# arm_new.net
KiCad netlist of a schematic drawn in EAGLE
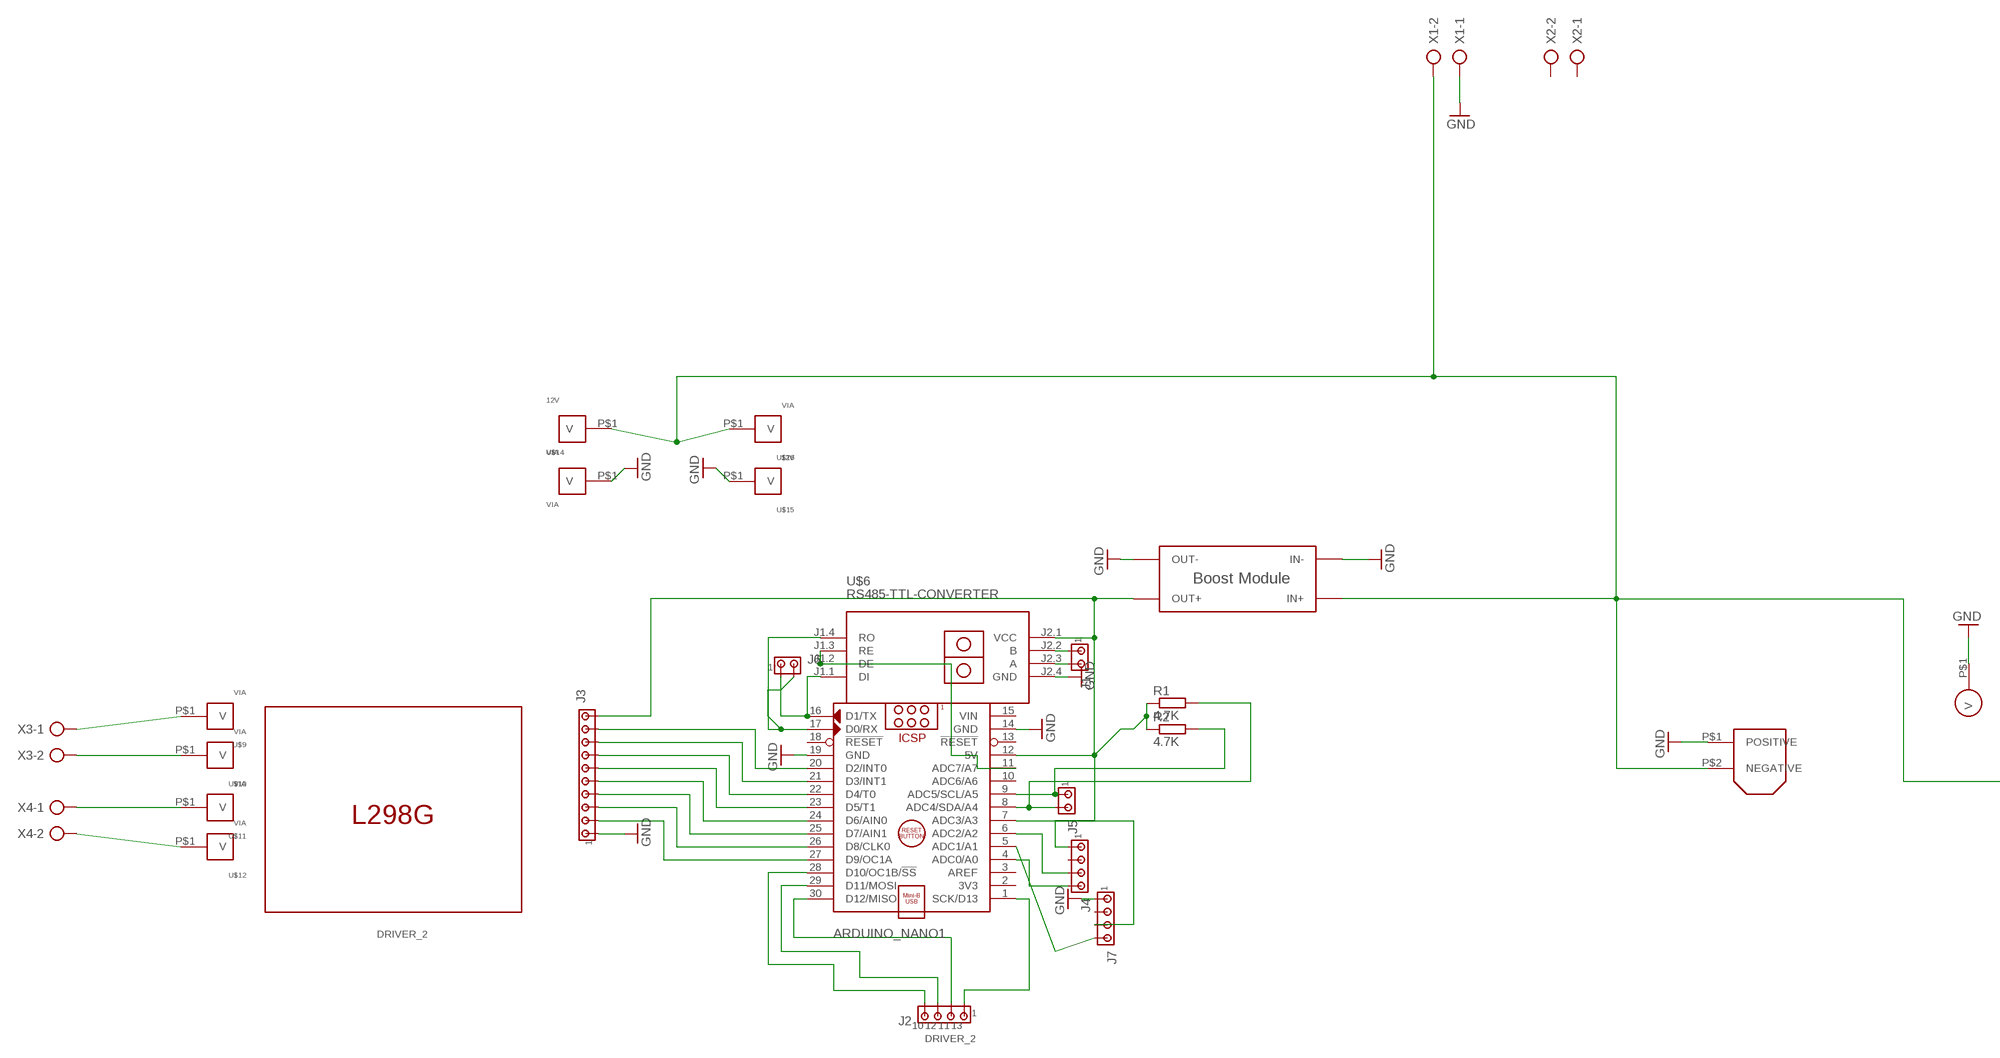
[diagram p0: schematic, sheet 1, part 1 of 2]
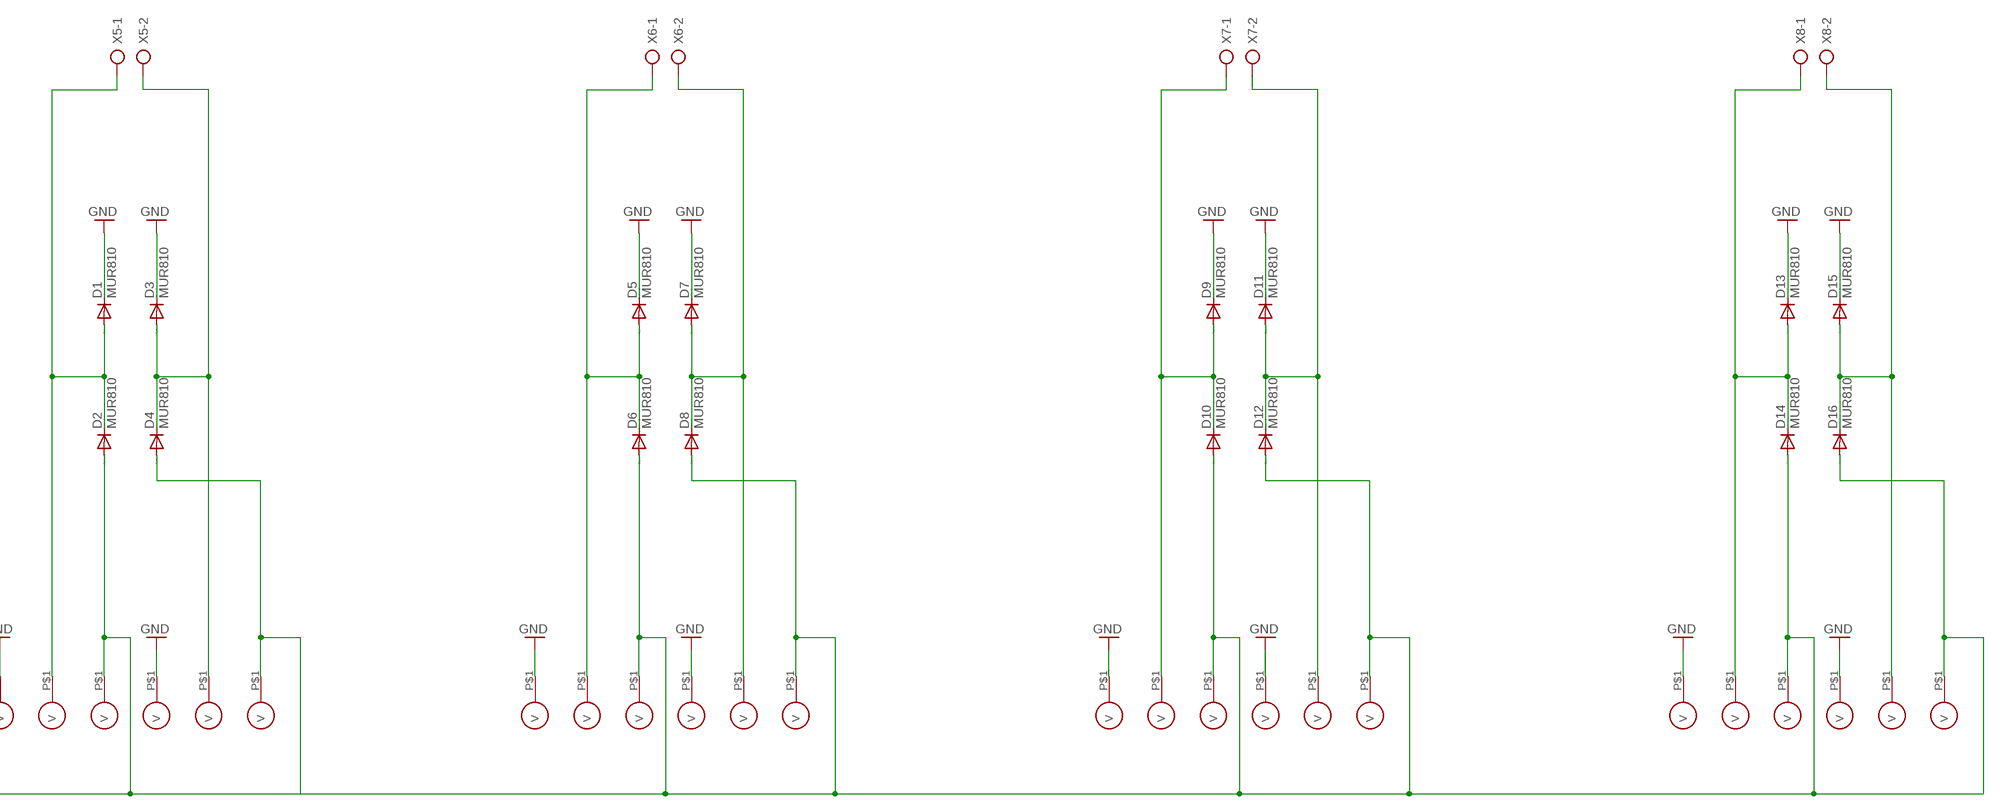
[diagram p1: schematic, sheet 1, part 2 of 2]

(export (version "E")
  (design (tool "Eeschema 10.0.6"))
  (components
    (comp (ref "12V")
      (value "VIA")
      (footprint "eagle-import:VIA")
      (libsource (lib "eagle-import") (part "VIA"))
    )
    (comp (ref "ARDUINO_NANO1")
      (value "ARDUINO_NANO")
      (footprint "eagle-import:ARDUINO_NANO")
      (libsource (lib "eagle-import") (part "ARDUINO_NANO"))
    )
    (comp (ref "D1")
      (value "MUR810")
      (footprint "eagle-import:TO220ACS")
      (libsource (lib "eagle-import") (part "MUR810"))
    )
    (comp (ref "D2")
      (value "MUR810")
      (footprint "eagle-import:TO220ACS")
      (libsource (lib "eagle-import") (part "MUR810"))
    )
    (comp (ref "D3")
      (value "MUR810")
      (footprint "eagle-import:TO220ACS")
      (libsource (lib "eagle-import") (part "MUR810"))
    )
    (comp (ref "D4")
      (value "MUR810")
      (footprint "eagle-import:TO220ACS")
      (libsource (lib "eagle-import") (part "MUR810"))
    )
    (comp (ref "D5")
      (value "MUR810")
      (footprint "eagle-import:TO220ACS")
      (libsource (lib "eagle-import") (part "MUR810"))
    )
    (comp (ref "D6")
      (value "MUR810")
      (footprint "eagle-import:TO220ACS")
      (libsource (lib "eagle-import") (part "MUR810"))
    )
    (comp (ref "D7")
      (value "MUR810")
      (footprint "eagle-import:TO220ACS")
      (libsource (lib "eagle-import") (part "MUR810"))
    )
    (comp (ref "D8")
      (value "MUR810")
      (footprint "eagle-import:TO220ACS")
      (libsource (lib "eagle-import") (part "MUR810"))
    )
    (comp (ref "D9")
      (value "MUR810")
      (footprint "eagle-import:TO220ACS")
      (libsource (lib "eagle-import") (part "MUR810"))
    )
    (comp (ref "D10")
      (value "MUR810")
      (footprint "eagle-import:TO220ACS")
      (libsource (lib "eagle-import") (part "MUR810"))
    )
    (comp (ref "D11")
      (value "MUR810")
      (footprint "eagle-import:TO220ACS")
      (libsource (lib "eagle-import") (part "MUR810"))
    )
    (comp (ref "D12")
      (value "MUR810")
      (footprint "eagle-import:TO220ACS")
      (libsource (lib "eagle-import") (part "MUR810"))
    )
    (comp (ref "D13")
      (value "MUR810")
      (footprint "eagle-import:TO220ACS")
      (libsource (lib "eagle-import") (part "MUR810"))
    )
    (comp (ref "D14")
      (value "MUR810")
      (footprint "eagle-import:TO220ACS")
      (libsource (lib "eagle-import") (part "MUR810"))
    )
    (comp (ref "D15")
      (value "MUR810")
      (footprint "eagle-import:TO220ACS")
      (libsource (lib "eagle-import") (part "MUR810"))
    )
    (comp (ref "D16")
      (value "MUR810")
      (footprint "eagle-import:TO220ACS")
      (libsource (lib "eagle-import") (part "MUR810"))
    )
    (comp (ref "J1")
      (value "MTA02-100")
      (footprint "eagle-import:10X02MTA")
      (libsource (lib "eagle-import") (part "MTA02-100"))
    )
    (comp (ref "J2")
      (value "MTA04-100")
      (footprint "eagle-import:10X04MTA")
      (libsource (lib "eagle-import") (part "MTA04-100"))
    )
    (comp (ref "J3")
      (value "MTA10-100")
      (footprint "eagle-import:10X10MTA")
      (libsource (lib "eagle-import") (part "MTA10-100"))
    )
    (comp (ref "J4")
      (value "MTA04-100")
      (footprint "eagle-import:10X04MTA")
      (libsource (lib "eagle-import") (part "MTA04-100"))
    )
    (comp (ref "J5")
      (value "MTA02-100")
      (footprint "eagle-import:10X02MTA")
      (libsource (lib "eagle-import") (part "MTA02-100"))
    )
    (comp (ref "J6")
      (value "MTA02-100")
      (footprint "eagle-import:10X02MTA")
      (libsource (lib "eagle-import") (part "MTA02-100"))
    )
    (comp (ref "J7")
      (value "MTA04-100")
      (footprint "eagle-import:10X04MTA")
      (libsource (lib "eagle-import") (part "MTA04-100"))
    )
    (comp (ref "NO")
      (value "NO")
      (footprint "eagle-import:ROUND_VIA")
      (libsource (lib "eagle-import") (part "ROUND_VIA"))
    )
    (comp (ref "NO1")
      (value "NO")
      (footprint "eagle-import:ROUND_VIA")
      (libsource (lib "eagle-import") (part "ROUND_VIA"))
    )
    (comp (ref "NO2")
      (value "NO")
      (footprint "eagle-import:ROUND_VIA")
      (libsource (lib "eagle-import") (part "ROUND_VIA"))
    )
    (comp (ref "NO3")
      (value "NO")
      (footprint "eagle-import:ROUND_VIA")
      (libsource (lib "eagle-import") (part "ROUND_VIA"))
    )
    (comp (ref "R1")
      (value "4.7K")
      (footprint "eagle-import:0204_7")
      (libsource (lib "eagle-import") (part "R-EU_0204/7"))
    )
    (comp (ref "R2")
      (value "4.7K")
      (footprint "eagle-import:0204_7")
      (libsource (lib "eagle-import") (part "R-EU_0204/7"))
    )
    (comp (ref "U$1")
      (value "BOOST_MODULE")
      (footprint "eagle-import:BOOST_MODULE")
      (libsource (lib "eagle-import") (part "BOOST_MODULE"))
    )
    (comp (ref "U$2")
      (value "XT60")
      (footprint "eagle-import:CONNECTOR")
      (libsource (lib "eagle-import") (part "XT60"))
    )
    (comp (ref "U$4")
      (value "L298G")
      (footprint "eagle-import:L298G")
      (libsource (lib "eagle-import") (part "L298G"))
    )
    (comp (ref "U$6")
      (value "RS485-TTL-CONVERTER")
      (footprint "eagle-import:RS485-TTL-CONVERTER")
      (libsource (lib "eagle-import") (part "RS485-TTL-CONVERTER"))
    )
    (comp (ref "U$9")
      (value "VIA")
      (footprint "eagle-import:VIA")
      (libsource (lib "eagle-import") (part "VIA"))
    )
    (comp (ref "U$10")
      (value "VIA")
      (footprint "eagle-import:VIA")
      (libsource (lib "eagle-import") (part "VIA"))
    )
    (comp (ref "U$11")
      (value "VIA")
      (footprint "eagle-import:VIA")
      (libsource (lib "eagle-import") (part "VIA"))
    )
    (comp (ref "U$12")
      (value "VIA")
      (footprint "eagle-import:VIA")
      (libsource (lib "eagle-import") (part "VIA"))
    )
    (comp (ref "U$14")
      (value "VIA")
      (footprint "eagle-import:VIA")
      (libsource (lib "eagle-import") (part "VIA"))
    )
    (comp (ref "U$15")
      (value "12V")
      (footprint "eagle-import:VIA")
      (libsource (lib "eagle-import") (part "VIA"))
    )
    (comp (ref "U$16")
      (value "VIA")
      (footprint "eagle-import:VIA")
      (libsource (lib "eagle-import") (part "VIA"))
    )
    (comp (ref "U$17")
      (value "ROUND_VIA")
      (footprint "eagle-import:ROUND_VIA")
      (libsource (lib "eagle-import") (part "ROUND_VIA"))
    )
    (comp (ref "U$18")
      (value "ROUND_VIA")
      (footprint "eagle-import:ROUND_VIA")
      (libsource (lib "eagle-import") (part "ROUND_VIA"))
    )
    (comp (ref "U$19")
      (value "ROUND_VIA")
      (footprint "eagle-import:ROUND_VIA")
      (libsource (lib "eagle-import") (part "ROUND_VIA"))
    )
    (comp (ref "U$20")
      (value "ROUND_VIA")
      (footprint "eagle-import:ROUND_VIA")
      (libsource (lib "eagle-import") (part "ROUND_VIA"))
    )
    (comp (ref "U$21")
      (value "ROUND_VIA")
      (footprint "eagle-import:ROUND_VIA")
      (libsource (lib "eagle-import") (part "ROUND_VIA"))
    )
    (comp (ref "U$22")
      (value "ROUND_VIA")
      (footprint "eagle-import:ROUND_VIA")
      (libsource (lib "eagle-import") (part "ROUND_VIA"))
    )
    (comp (ref "U$23")
      (value "ROUND_VIA")
      (footprint "eagle-import:ROUND_VIA")
      (libsource (lib "eagle-import") (part "ROUND_VIA"))
    )
    (comp (ref "U$24")
      (value "ROUND_VIA")
      (footprint "eagle-import:ROUND_VIA")
      (libsource (lib "eagle-import") (part "ROUND_VIA"))
    )
    (comp (ref "U$25")
      (value "ROUND_VIA")
      (footprint "eagle-import:ROUND_VIA")
      (libsource (lib "eagle-import") (part "ROUND_VIA"))
    )
    (comp (ref "U$26")
      (value "ROUND_VIA")
      (footprint "eagle-import:ROUND_VIA")
      (libsource (lib "eagle-import") (part "ROUND_VIA"))
    )
    (comp (ref "U$27")
      (value "ROUND_VIA")
      (footprint "eagle-import:ROUND_VIA")
      (libsource (lib "eagle-import") (part "ROUND_VIA"))
    )
    (comp (ref "U$28")
      (value "ROUND_VIA")
      (footprint "eagle-import:ROUND_VIA")
      (libsource (lib "eagle-import") (part "ROUND_VIA"))
    )
    (comp (ref "U$29")
      (value "ROUND_VIA")
      (footprint "eagle-import:ROUND_VIA")
      (libsource (lib "eagle-import") (part "ROUND_VIA"))
    )
    (comp (ref "U$30")
      (value "ROUND_VIA")
      (footprint "eagle-import:ROUND_VIA")
      (libsource (lib "eagle-import") (part "ROUND_VIA"))
    )
    (comp (ref "U$31")
      (value "ROUND_VIA")
      (footprint "eagle-import:ROUND_VIA")
      (libsource (lib "eagle-import") (part "ROUND_VIA"))
    )
    (comp (ref "U$32")
      (value "ROUND_VIA")
      (footprint "eagle-import:ROUND_VIA")
      (libsource (lib "eagle-import") (part "ROUND_VIA"))
    )
    (comp (ref "U$33")
      (value "ROUND_VIA")
      (footprint "eagle-import:ROUND_VIA")
      (libsource (lib "eagle-import") (part "ROUND_VIA"))
    )
    (comp (ref "U$34")
      (value "ROUND_VIA")
      (footprint "eagle-import:ROUND_VIA")
      (libsource (lib "eagle-import") (part "ROUND_VIA"))
    )
    (comp (ref "U$35")
      (value "ROUND_VIA")
      (footprint "eagle-import:ROUND_VIA")
      (libsource (lib "eagle-import") (part "ROUND_VIA"))
    )
    (comp (ref "U$36")
      (value "ROUND_VIA")
      (footprint "eagle-import:ROUND_VIA")
      (libsource (lib "eagle-import") (part "ROUND_VIA"))
    )
    (comp (ref "X1")
      (value "AK300/2")
      (footprint "eagle-import:AK300_2")
      (libsource (lib "eagle-import") (part "AK300/2"))
    )
    (comp (ref "X2")
      (value "AK300/2")
      (footprint "eagle-import:AK300_2")
      (libsource (lib "eagle-import") (part "AK300/2"))
    )
    (comp (ref "X3")
      (value "AK300/2")
      (footprint "eagle-import:AK300_2")
      (libsource (lib "eagle-import") (part "AK300/2"))
    )
    (comp (ref "X4")
      (value "AK300/2")
      (footprint "eagle-import:AK300_2")
      (libsource (lib "eagle-import") (part "AK300/2"))
    )
    (comp (ref "X5")
      (value "AK300/2")
      (footprint "eagle-import:AK300_2")
      (libsource (lib "eagle-import") (part "AK300/2"))
    )
    (comp (ref "X6")
      (value "AK300/2")
      (footprint "eagle-import:AK300_2")
      (libsource (lib "eagle-import") (part "AK300/2"))
    )
    (comp (ref "X7")
      (value "AK300/2")
      (footprint "eagle-import:AK300_2")
      (libsource (lib "eagle-import") (part "AK300/2"))
    )
    (comp (ref "X8")
      (value "AK300/2")
      (footprint "eagle-import:AK300_2")
      (libsource (lib "eagle-import") (part "AK300/2"))
    )
  )
  (nets
    (net (code "1") (name "/VIN") (class "Default")
      (node (ref "ARDUINO_NANO1") (pin "15") (pinfunction "VIN_15") (pintype "power_in"))
    )
    (net (code "2") (name "GND") (class "Default")
      (node (ref "ARDUINO_NANO1") (pin "14") (pinfunction "GND_14") (pintype "power_in"))
      (node (ref "ARDUINO_NANO1") (pin "19") (pinfunction "GND_19") (pintype "power_in"))
      (node (ref "D1") (pin "C") (pinfunction "C_C") (pintype "passive"))
      (node (ref "D11") (pin "C") (pinfunction "C_C") (pintype "passive"))
      (node (ref "D13") (pin "C") (pinfunction "C_C") (pintype "passive"))
      (node (ref "D15") (pin "C") (pinfunction "C_C") (pintype "passive"))
      (node (ref "D3") (pin "C") (pinfunction "C_C") (pintype "passive"))
      (node (ref "D5") (pin "C") (pinfunction "C_C") (pintype "passive"))
      (node (ref "D7") (pin "C") (pinfunction "C_C") (pintype "passive"))
      (node (ref "D9") (pin "C") (pinfunction "C_C") (pintype "passive"))
      (node (ref "J3") (pin "1") (pinfunction "1_1") (pintype "passive"))
      (node (ref "J7") (pin "1") (pinfunction "1_1") (pintype "passive"))
      (node (ref "NO") (pin "P$1") (pinfunction "V_P$1") (pintype "bidirectional"))
      (node (ref "NO1") (pin "P$1") (pinfunction "V_P$1") (pintype "bidirectional"))
      (node (ref "NO2") (pin "P$1") (pinfunction "V_P$1") (pintype "bidirectional"))
      (node (ref "NO3") (pin "P$1") (pinfunction "V_P$1") (pintype "bidirectional"))
      (node (ref "U$1") (pin "IN-") (pinfunction "IN-_IN-") (pintype "bidirectional"))
      (node (ref "U$1") (pin "OUT-") (pinfunction "OUT-_OUT-") (pintype "bidirectional"))
      (node (ref "U$14") (pin "P$1") (pinfunction "V_P$1") (pintype "bidirectional"))
      (node (ref "U$15") (pin "P$1") (pinfunction "V_P$1") (pintype "bidirectional"))
      (node (ref "U$2") (pin "P$1") (pinfunction "POSITIVE_P$1") (pintype "bidirectional"))
      (node (ref "U$20") (pin "P$1") (pinfunction "V_P$1") (pintype "bidirectional"))
      (node (ref "U$24") (pin "P$1") (pinfunction "V_P$1") (pintype "bidirectional"))
      (node (ref "U$29") (pin "P$1") (pinfunction "V_P$1") (pintype "bidirectional"))
      (node (ref "U$34") (pin "P$1") (pinfunction "V_P$1") (pintype "bidirectional"))
      (node (ref "U$6") (pin "J2.4") (pinfunction "GND_J2.4") (pintype "power_in"))
      (node (ref "X1") (pin "1") (pinfunction "KL_1") (pintype "passive"))
    )
    (net (code "3") (name "Net-(12V-V)") (class "Default")
      (node (ref "12V") (pin "P$1") (pinfunction "V_P$1") (pintype "bidirectional"))
      (node (ref "D10") (pin "A") (pinfunction "A_A") (pintype "passive"))
      (node (ref "D12") (pin "A") (pinfunction "A_A") (pintype "passive"))
      (node (ref "D14") (pin "A") (pinfunction "A_A") (pintype "passive"))
      (node (ref "D16") (pin "A") (pinfunction "A_A") (pintype "passive"))
      (node (ref "D2") (pin "A") (pinfunction "A_A") (pintype "passive"))
      (node (ref "D4") (pin "A") (pinfunction "A_A") (pintype "passive"))
      (node (ref "D6") (pin "A") (pinfunction "A_A") (pintype "passive"))
      (node (ref "D8") (pin "A") (pinfunction "A_A") (pintype "passive"))
      (node (ref "U$1") (pin "IN+") (pinfunction "IN+_IN+") (pintype "bidirectional"))
      (node (ref "U$16") (pin "P$1") (pinfunction "V_P$1") (pintype "bidirectional"))
      (node (ref "U$19") (pin "P$1") (pinfunction "V_P$1") (pintype "bidirectional"))
      (node (ref "U$2") (pin "P$2") (pinfunction "NEGATIVE_P$2") (pintype "bidirectional"))
      (node (ref "U$22") (pin "P$1") (pinfunction "V_P$1") (pintype "bidirectional"))
      (node (ref "U$23") (pin "P$1") (pinfunction "V_P$1") (pintype "bidirectional"))
      (node (ref "U$26") (pin "P$1") (pinfunction "V_P$1") (pintype "bidirectional"))
      (node (ref "U$28") (pin "P$1") (pinfunction "V_P$1") (pintype "bidirectional"))
      (node (ref "U$31") (pin "P$1") (pinfunction "V_P$1") (pintype "bidirectional"))
      (node (ref "U$33") (pin "P$1") (pinfunction "V_P$1") (pintype "bidirectional"))
      (node (ref "U$36") (pin "P$1") (pinfunction "V_P$1") (pintype "bidirectional"))
      (node (ref "X1") (pin "2") (pinfunction "KL_2") (pintype "passive"))
    )
    (net (code "4") (name "Net-(ARDUINO_NANO1-5V)") (class "Default")
      (node (ref "ARDUINO_NANO1") (pin "12") (pinfunction "5V_12") (pintype "power_in"))
      (node (ref "J3") (pin "10") (pinfunction "10_10") (pintype "passive"))
      (node (ref "J4") (pin "1") (pinfunction "1_1") (pintype "passive"))
      (node (ref "R1") (pin "1") (pinfunction "1_1") (pintype "passive"))
      (node (ref "R2") (pin "1") (pinfunction "1_1") (pintype "passive"))
      (node (ref "U$1") (pin "OUT+") (pinfunction "OUT+_OUT+") (pintype "bidirectional"))
      (node (ref "U$6") (pin "J2.1") (pinfunction "VCC_J2.1") (pintype "power_in"))
    )
    (net (code "5") (name "Net-(ARDUINO_NANO1-ADC0{slash}A0)") (class "Default")
      (node (ref "ARDUINO_NANO1") (pin "4") (pinfunction "ADC0/A0_4") (pintype "bidirectional"))
      (node (ref "J4") (pin "4") (pinfunction "4_4") (pintype "passive"))
    )
    (net (code "6") (name "Net-(ARDUINO_NANO1-ADC1{slash}A1)") (class "Default")
      (node (ref "ARDUINO_NANO1") (pin "5") (pinfunction "ADC1/A1_5") (pintype "bidirectional"))
      (node (ref "J7") (pin "4") (pinfunction "4_4") (pintype "passive"))
    )
    (net (code "7") (name "Net-(ARDUINO_NANO1-ADC2{slash}A2)") (class "Default")
      (node (ref "ARDUINO_NANO1") (pin "6") (pinfunction "ADC2/A2_6") (pintype "bidirectional"))
      (node (ref "J4") (pin "3") (pinfunction "3_3") (pintype "passive"))
    )
    (net (code "8") (name "Net-(ARDUINO_NANO1-ADC3{slash}A3)") (class "Default")
      (node (ref "ARDUINO_NANO1") (pin "7") (pinfunction "ADC3/A3_7") (pintype "bidirectional"))
      (node (ref "J7") (pin "3") (pinfunction "3_3") (pintype "passive"))
    )
    (net (code "9") (name "Net-(ARDUINO_NANO1-ADC4{slash}SDA{slash}A4)") (class "Default")
      (node (ref "ARDUINO_NANO1") (pin "8") (pinfunction "ADC4/SDA/A4_8") (pintype "bidirectional"))
      (node (ref "J5") (pin "2") (pinfunction "2_2") (pintype "passive"))
      (node (ref "R1") (pin "2") (pinfunction "2_2") (pintype "passive"))
    )
    (net (code "10") (name "Net-(ARDUINO_NANO1-ADC5{slash}SCL{slash}A5)") (class "Default")
      (node (ref "ARDUINO_NANO1") (pin "9") (pinfunction "ADC5/SCL/A5_9") (pintype "bidirectional"))
      (node (ref "J5") (pin "1") (pinfunction "1_1") (pintype "passive"))
      (node (ref "R2") (pin "2") (pinfunction "2_2") (pintype "passive"))
    )
    (net (code "11") (name "Net-(ARDUINO_NANO1-ADC7{slash}A7)") (class "Default")
      (node (ref "ARDUINO_NANO1") (pin "11") (pinfunction "ADC7/A7_11") (pintype "bidirectional"))
      (node (ref "U$6") (pin "J1.2") (pinfunction "DE_J1.2") (pintype "passive"))
      (node (ref "U$6") (pin "J1.3") (pinfunction "RE_J1.3") (pintype "passive"))
    )
    (net (code "12") (name "Net-(ARDUINO_NANO1-D0{slash}RX)") (class "Default")
      (node (ref "ARDUINO_NANO1") (pin "17") (pinfunction "D0/RX_17") (pintype "bidirectional"))
      (node (ref "J6") (pin "2") (pinfunction "2_2") (pintype "passive"))
      (node (ref "U$6") (pin "J1.4") (pinfunction "RO_J1.4") (pintype "passive"))
    )
    (net (code "13") (name "Net-(ARDUINO_NANO1-D1{slash}TX)") (class "Default")
      (node (ref "ARDUINO_NANO1") (pin "16") (pinfunction "D1/TX_16") (pintype "bidirectional"))
      (node (ref "J6") (pin "1") (pinfunction "1_1") (pintype "passive"))
      (node (ref "U$6") (pin "J1.1") (pinfunction "DI_J1.1") (pintype "passive"))
    )
    (net (code "14") (name "Net-(ARDUINO_NANO1-D2{slash}INT0)") (class "Default")
      (node (ref "ARDUINO_NANO1") (pin "20") (pinfunction "D2/INT0_20") (pintype "bidirectional"))
      (node (ref "J3") (pin "9") (pinfunction "9_9") (pintype "passive"))
    )
    (net (code "15") (name "Net-(ARDUINO_NANO1-D3{slash}INT1)") (class "Default")
      (node (ref "ARDUINO_NANO1") (pin "21") (pinfunction "D3/INT1_21") (pintype "bidirectional"))
      (node (ref "J3") (pin "8") (pinfunction "8_8") (pintype "passive"))
    )
    (net (code "16") (name "Net-(ARDUINO_NANO1-D4{slash}T0)") (class "Default")
      (node (ref "ARDUINO_NANO1") (pin "22") (pinfunction "D4/T0_22") (pintype "bidirectional"))
      (node (ref "J3") (pin "7") (pinfunction "7_7") (pintype "passive"))
    )
    (net (code "17") (name "Net-(ARDUINO_NANO1-D5{slash}T1)") (class "Default")
      (node (ref "ARDUINO_NANO1") (pin "23") (pinfunction "D5/T1_23") (pintype "bidirectional"))
      (node (ref "J3") (pin "6") (pinfunction "6_6") (pintype "passive"))
    )
    (net (code "18") (name "Net-(ARDUINO_NANO1-D6{slash}AIN0)") (class "Default")
      (node (ref "ARDUINO_NANO1") (pin "24") (pinfunction "D6/AIN0_24") (pintype "bidirectional"))
      (node (ref "J3") (pin "5") (pinfunction "5_5") (pintype "passive"))
    )
    (net (code "19") (name "Net-(ARDUINO_NANO1-D7{slash}AIN1)") (class "Default")
      (node (ref "ARDUINO_NANO1") (pin "25") (pinfunction "D7/AIN1_25") (pintype "bidirectional"))
      (node (ref "J3") (pin "4") (pinfunction "4_4") (pintype "passive"))
    )
    (net (code "20") (name "Net-(ARDUINO_NANO1-D8{slash}CLK0)") (class "Default")
      (node (ref "ARDUINO_NANO1") (pin "26") (pinfunction "D8/CLK0_26") (pintype "bidirectional"))
      (node (ref "J3") (pin "3") (pinfunction "3_3") (pintype "passive"))
    )
    (net (code "21") (name "Net-(ARDUINO_NANO1-D9{slash}OC1A)") (class "Default")
      (node (ref "ARDUINO_NANO1") (pin "27") (pinfunction "D9/OC1A_27") (pintype "bidirectional"))
      (node (ref "J3") (pin "2") (pinfunction "2_2") (pintype "passive"))
    )
    (net (code "22") (name "Net-(ARDUINO_NANO1-D10{slash}OC1B{slash}~{SS})") (class "Default")
      (node (ref "ARDUINO_NANO1") (pin "28") (pinfunction "D10/OC1B/~{SS}_28") (pintype "bidirectional"))
      (node (ref "J2") (pin "4") (pinfunction "4_4") (pintype "passive"))
    )
    (net (code "23") (name "Net-(ARDUINO_NANO1-D11{slash}MOSI)") (class "Default")
      (node (ref "ARDUINO_NANO1") (pin "29") (pinfunction "D11/MOSI_29") (pintype "bidirectional"))
      (node (ref "J2") (pin "3") (pinfunction "3_3") (pintype "passive"))
    )
    (net (code "24") (name "Net-(ARDUINO_NANO1-D12{slash}MISO)") (class "Default")
      (node (ref "ARDUINO_NANO1") (pin "30") (pinfunction "D12/MISO_30") (pintype "bidirectional"))
      (node (ref "J2") (pin "2") (pinfunction "2_2") (pintype "passive"))
    )
    (net (code "25") (name "Net-(ARDUINO_NANO1-SCK{slash}D13)") (class "Default")
      (node (ref "ARDUINO_NANO1") (pin "1") (pinfunction "SCK/D13_1") (pintype "bidirectional"))
      (node (ref "J2") (pin "1") (pinfunction "1_1") (pintype "passive"))
    )
    (net (code "26") (name "Net-(U$6-A)") (class "Default")
      (node (ref "J1") (pin "2") (pinfunction "2_2") (pintype "passive"))
      (node (ref "U$6") (pin "J2.3") (pinfunction "A_J2.3") (pintype "passive"))
    )
    (net (code "27") (name "Net-(U$6-B)") (class "Default")
      (node (ref "J1") (pin "1") (pinfunction "1_1") (pintype "passive"))
      (node (ref "U$6") (pin "J2.2") (pinfunction "B_J2.2") (pintype "passive"))
    )
    (net (code "28") (name "Net-(U$9-V)") (class "Default")
      (node (ref "U$9") (pin "P$1") (pinfunction "V_P$1") (pintype "bidirectional"))
      (node (ref "X3") (pin "1") (pinfunction "KL_1") (pintype "passive"))
    )
    (net (code "29") (name "Net-(U$10-V)") (class "Default")
      (node (ref "U$10") (pin "P$1") (pinfunction "V_P$1") (pintype "bidirectional"))
      (node (ref "X3") (pin "2") (pinfunction "KL_2") (pintype "passive"))
    )
    (net (code "30") (name "Net-(U$11-V)") (class "Default")
      (node (ref "U$11") (pin "P$1") (pinfunction "V_P$1") (pintype "bidirectional"))
      (node (ref "X4") (pin "1") (pinfunction "KL_1") (pintype "passive"))
    )
    (net (code "31") (name "Net-(U$12-V)") (class "Default")
      (node (ref "U$12") (pin "P$1") (pinfunction "V_P$1") (pintype "bidirectional"))
      (node (ref "X4") (pin "2") (pinfunction "KL_2") (pintype "passive"))
    )
    (net (code "32") (name "Net-(U$17-V)") (class "Default")
      (node (ref "D5") (pin "A") (pinfunction "A_A") (pintype "passive"))
      (node (ref "D6") (pin "C") (pinfunction "C_C") (pintype "passive"))
      (node (ref "U$17") (pin "P$1") (pinfunction "V_P$1") (pintype "bidirectional"))
      (node (ref "X6") (pin "1") (pinfunction "KL_1") (pintype "passive"))
    )
    (net (code "33") (name "Net-(U$18-V)") (class "Default")
      (node (ref "D1") (pin "A") (pinfunction "A_A") (pintype "passive"))
      (node (ref "D2") (pin "C") (pinfunction "C_C") (pintype "passive"))
      (node (ref "U$18") (pin "P$1") (pinfunction "V_P$1") (pintype "bidirectional"))
      (node (ref "X5") (pin "1") (pinfunction "KL_1") (pintype "passive"))
    )
    (net (code "34") (name "Net-(U$21-V)") (class "Default")
      (node (ref "D3") (pin "A") (pinfunction "A_A") (pintype "passive"))
      (node (ref "D4") (pin "C") (pinfunction "C_C") (pintype "passive"))
      (node (ref "U$21") (pin "P$1") (pinfunction "V_P$1") (pintype "bidirectional"))
      (node (ref "X5") (pin "2") (pinfunction "KL_2") (pintype "passive"))
    )
    (net (code "35") (name "Net-(U$25-V)") (class "Default")
      (node (ref "D7") (pin "A") (pinfunction "A_A") (pintype "passive"))
      (node (ref "D8") (pin "C") (pinfunction "C_C") (pintype "passive"))
      (node (ref "U$25") (pin "P$1") (pinfunction "V_P$1") (pintype "bidirectional"))
      (node (ref "X6") (pin "2") (pinfunction "KL_2") (pintype "passive"))
    )
    (net (code "36") (name "Net-(U$27-V)") (class "Default")
      (node (ref "D10") (pin "C") (pinfunction "C_C") (pintype "passive"))
      (node (ref "D9") (pin "A") (pinfunction "A_A") (pintype "passive"))
      (node (ref "U$27") (pin "P$1") (pinfunction "V_P$1") (pintype "bidirectional"))
      (node (ref "X7") (pin "1") (pinfunction "KL_1") (pintype "passive"))
    )
    (net (code "37") (name "Net-(U$30-V)") (class "Default")
      (node (ref "D11") (pin "A") (pinfunction "A_A") (pintype "passive"))
      (node (ref "D12") (pin "C") (pinfunction "C_C") (pintype "passive"))
      (node (ref "U$30") (pin "P$1") (pinfunction "V_P$1") (pintype "bidirectional"))
      (node (ref "X7") (pin "2") (pinfunction "KL_2") (pintype "passive"))
    )
    (net (code "38") (name "Net-(U$32-V)") (class "Default")
      (node (ref "D13") (pin "A") (pinfunction "A_A") (pintype "passive"))
      (node (ref "D14") (pin "C") (pinfunction "C_C") (pintype "passive"))
      (node (ref "U$32") (pin "P$1") (pinfunction "V_P$1") (pintype "bidirectional"))
      (node (ref "X8") (pin "1") (pinfunction "KL_1") (pintype "passive"))
    )
    (net (code "39") (name "Net-(U$35-V)") (class "Default")
      (node (ref "D15") (pin "A") (pinfunction "A_A") (pintype "passive"))
      (node (ref "D16") (pin "C") (pinfunction "C_C") (pintype "passive"))
      (node (ref "U$35") (pin "P$1") (pinfunction "V_P$1") (pintype "bidirectional"))
      (node (ref "X8") (pin "2") (pinfunction "KL_2") (pintype "passive"))
    )
    (net (code "40") (name "unconnected-(ARDUINO_NANO1-3V3-Pad2)") (class "Default")
      (node (ref "ARDUINO_NANO1") (pin "2") (pinfunction "3V3_2") (pintype "output"))
    )
    (net (code "41") (name "unconnected-(ARDUINO_NANO1-ADC6{slash}A6-Pad10)") (class "Default")
      (node (ref "ARDUINO_NANO1") (pin "10") (pinfunction "ADC6/A6_10") (pintype "bidirectional"))
    )
    (net (code "42") (name "unconnected-(ARDUINO_NANO1-AREF-Pad3)") (class "Default")
      (node (ref "ARDUINO_NANO1") (pin "3") (pinfunction "AREF_3") (pintype "input"))
    )
    (net (code "43") (name "unconnected-(ARDUINO_NANO1-~{RESET}-Pad13)") (class "Default")
      (node (ref "ARDUINO_NANO1") (pin "13") (pinfunction "~{RESET}_13") (pintype "input"))
    )
    (net (code "44") (name "unconnected-(ARDUINO_NANO1-~{RESET}-Pad18)") (class "Default")
      (node (ref "ARDUINO_NANO1") (pin "18") (pinfunction "~{RESET}_18") (pintype "input"))
    )
    (net (code "45") (name "unconnected-(J4-Pad2)") (class "Default")
      (node (ref "J4") (pin "2") (pinfunction "2_2") (pintype "passive"))
    )
    (net (code "46") (name "unconnected-(J7-Pad2)") (class "Default")
      (node (ref "J7") (pin "2") (pinfunction "2_2") (pintype "passive"))
    )
    (net (code "47") (name "unconnected-(X2A-KL-Pad1)") (class "Default")
      (node (ref "X2") (pin "1") (pinfunction "KL_1") (pintype "passive"))
    )
    (net (code "48") (name "unconnected-(X2B-KL-Pad2)") (class "Default")
      (node (ref "X2") (pin "2") (pinfunction "KL_2") (pintype "passive"))
    )
  )
)
